# Sheet1.net
KiCad netlist of a schematic drawn in Altium Designer
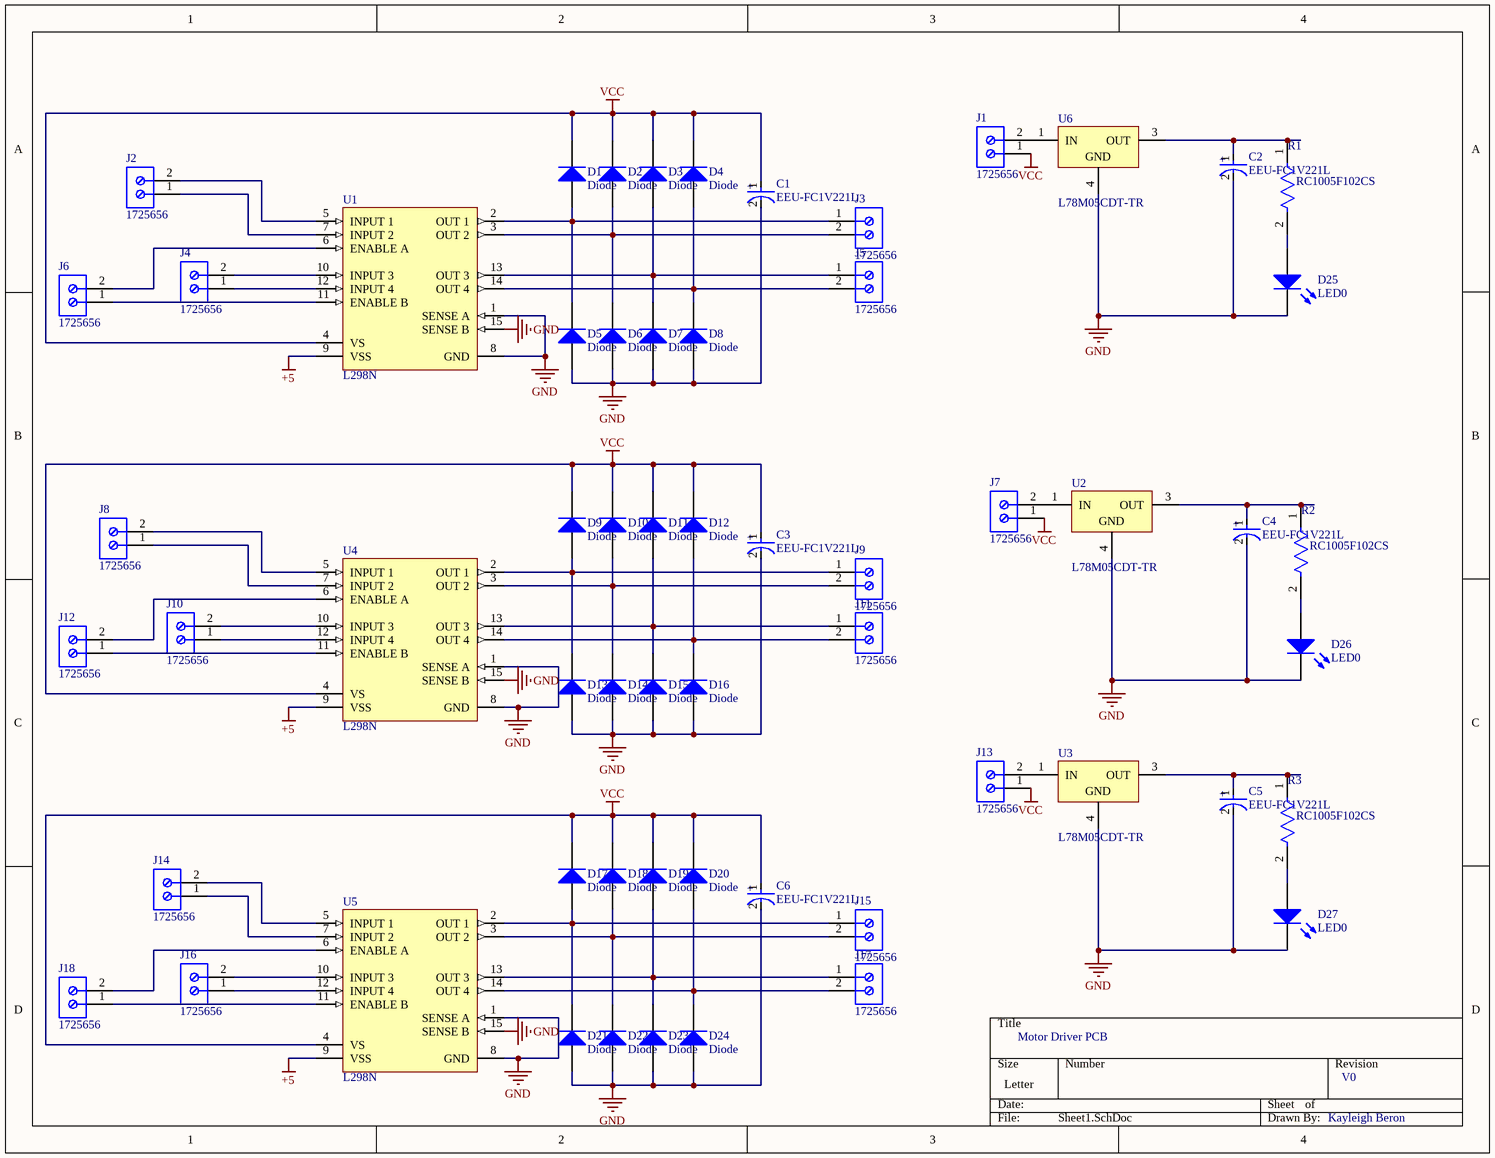
[diagram p0: Sheet1.SchDoc]

(export (version "E")
  (design (tool "Eeschema 10.0.6"))
  (components
    (comp (ref "C1")
      (value "EEU-FC1V221L")
      (footprint "FP-EEU-FC1V221L-MFG")
      (description "CAP ALUM 220UF 20% 35V RADIAL")
      (fields
        (field (name "OCTOPART") "https://octopart.com/eeu-fc1v221l-panasonic-39478519")
        (field (name "MANUFACTURER") "Panasonic Electronic Components")
      )
      (libsource (lib "Altium Content Vault") (part "385ce6c70a3ab0aa1e866f00bd8ed49"))
    )
    (comp (ref "C2")
      (value "EEU-FC1V221L")
      (footprint "FP-EEU-FC1V221L-MFG")
      (description "CAP ALUM 220UF 20% 35V RADIAL")
      (fields
        (field (name "OCTOPART") "https://octopart.com/eeu-fc1v221l-panasonic-39478519")
        (field (name "MANUFACTURER") "Panasonic Electronic Components")
      )
      (libsource (lib "Altium Content Vault") (part "385ce6c70a3ab0aa1e866f00bd8ed49"))
    )
    (comp (ref "C3")
      (value "EEU-FC1V221L")
      (footprint "FP-EEU-FC1V221L-MFG")
      (description "CAP ALUM 220UF 20% 35V RADIAL")
      (fields
        (field (name "OCTOPART") "https://octopart.com/eeu-fc1v221l-panasonic-39478519")
        (field (name "MANUFACTURER") "Panasonic Electronic Components")
      )
      (libsource (lib "Altium Content Vault") (part "385ce6c70a3ab0aa1e866f00bd8ed49"))
    )
    (comp (ref "C4")
      (value "EEU-FC1V221L")
      (footprint "FP-EEU-FC1V221L-MFG")
      (description "CAP ALUM 220UF 20% 35V RADIAL")
      (fields
        (field (name "OCTOPART") "https://octopart.com/eeu-fc1v221l-panasonic-39478519")
        (field (name "MANUFACTURER") "Panasonic Electronic Components")
      )
      (libsource (lib "Altium Content Vault") (part "385ce6c70a3ab0aa1e866f00bd8ed49"))
    )
    (comp (ref "C5")
      (value "EEU-FC1V221L")
      (footprint "FP-EEU-FC1V221L-MFG")
      (description "CAP ALUM 220UF 20% 35V RADIAL")
      (fields
        (field (name "OCTOPART") "https://octopart.com/eeu-fc1v221l-panasonic-39478519")
        (field (name "MANUFACTURER") "Panasonic Electronic Components")
      )
      (libsource (lib "Altium Content Vault") (part "385ce6c70a3ab0aa1e866f00bd8ed49"))
    )
    (comp (ref "C6")
      (value "EEU-FC1V221L")
      (footprint "FP-EEU-FC1V221L-MFG")
      (description "CAP ALUM 220UF 20% 35V RADIAL")
      (fields
        (field (name "OCTOPART") "https://octopart.com/eeu-fc1v221l-panasonic-39478519")
        (field (name "MANUFACTURER") "Panasonic Electronic Components")
      )
      (libsource (lib "Altium Content Vault") (part "385ce6c70a3ab0aa1e866f00bd8ed49"))
    )
    (comp (ref "D1")
      (value "Diode")
      (footprint "SMC")
      (description "Default Diode")
      (fields (field (name "PUBLISHER") "Altium Limited"))
      (libsource (lib "Miscellaneous Devices") (part "Diode"))
    )
    (comp (ref "D2")
      (value "Diode")
      (footprint "SMC")
      (description "Default Diode")
      (fields (field (name "PUBLISHER") "Altium Limited"))
      (libsource (lib "Miscellaneous Devices") (part "Diode"))
    )
    (comp (ref "D3")
      (value "Diode")
      (footprint "SMC")
      (description "Default Diode")
      (fields (field (name "PUBLISHER") "Altium Limited"))
      (libsource (lib "Miscellaneous Devices") (part "Diode"))
    )
    (comp (ref "D4")
      (value "Diode")
      (footprint "SMC")
      (description "Default Diode")
      (fields (field (name "PUBLISHER") "Altium Limited"))
      (libsource (lib "Miscellaneous Devices") (part "Diode"))
    )
    (comp (ref "D5")
      (value "Diode")
      (footprint "SMC")
      (description "Default Diode")
      (fields (field (name "PUBLISHER") "Altium Limited"))
      (libsource (lib "Miscellaneous Devices") (part "Diode"))
    )
    (comp (ref "D6")
      (value "Diode")
      (footprint "SMC")
      (description "Default Diode")
      (fields (field (name "PUBLISHER") "Altium Limited"))
      (libsource (lib "Miscellaneous Devices") (part "Diode"))
    )
    (comp (ref "D7")
      (value "Diode")
      (footprint "SMC")
      (description "Default Diode")
      (fields (field (name "PUBLISHER") "Altium Limited"))
      (libsource (lib "Miscellaneous Devices") (part "Diode"))
    )
    (comp (ref "D8")
      (value "Diode")
      (footprint "SMC")
      (description "Default Diode")
      (fields (field (name "PUBLISHER") "Altium Limited"))
      (libsource (lib "Miscellaneous Devices") (part "Diode"))
    )
    (comp (ref "D9")
      (value "Diode")
      (footprint "SMC")
      (description "Default Diode")
      (fields (field (name "PUBLISHER") "Altium Limited"))
      (libsource (lib "Miscellaneous Devices") (part "Diode"))
    )
    (comp (ref "D10")
      (value "Diode")
      (footprint "SMC")
      (description "Default Diode")
      (fields (field (name "PUBLISHER") "Altium Limited"))
      (libsource (lib "Miscellaneous Devices") (part "Diode"))
    )
    (comp (ref "D11")
      (value "Diode")
      (footprint "SMC")
      (description "Default Diode")
      (fields (field (name "PUBLISHER") "Altium Limited"))
      (libsource (lib "Miscellaneous Devices") (part "Diode"))
    )
    (comp (ref "D12")
      (value "Diode")
      (footprint "SMC")
      (description "Default Diode")
      (fields (field (name "PUBLISHER") "Altium Limited"))
      (libsource (lib "Miscellaneous Devices") (part "Diode"))
    )
    (comp (ref "D13")
      (value "Diode")
      (footprint "SMC")
      (description "Default Diode")
      (fields (field (name "PUBLISHER") "Altium Limited"))
      (libsource (lib "Miscellaneous Devices") (part "Diode"))
    )
    (comp (ref "D14")
      (value "Diode")
      (footprint "SMC")
      (description "Default Diode")
      (fields (field (name "PUBLISHER") "Altium Limited"))
      (libsource (lib "Miscellaneous Devices") (part "Diode"))
    )
    (comp (ref "D15")
      (value "Diode")
      (footprint "SMC")
      (description "Default Diode")
      (fields (field (name "PUBLISHER") "Altium Limited"))
      (libsource (lib "Miscellaneous Devices") (part "Diode"))
    )
    (comp (ref "D16")
      (value "Diode")
      (footprint "SMC")
      (description "Default Diode")
      (fields (field (name "PUBLISHER") "Altium Limited"))
      (libsource (lib "Miscellaneous Devices") (part "Diode"))
    )
    (comp (ref "D17")
      (value "Diode")
      (footprint "SMC")
      (description "Default Diode")
      (fields (field (name "PUBLISHER") "Altium Limited"))
      (libsource (lib "Miscellaneous Devices") (part "Diode"))
    )
    (comp (ref "D18")
      (value "Diode")
      (footprint "SMC")
      (description "Default Diode")
      (fields (field (name "PUBLISHER") "Altium Limited"))
      (libsource (lib "Miscellaneous Devices") (part "Diode"))
    )
    (comp (ref "D19")
      (value "Diode")
      (footprint "SMC")
      (description "Default Diode")
      (fields (field (name "PUBLISHER") "Altium Limited"))
      (libsource (lib "Miscellaneous Devices") (part "Diode"))
    )
    (comp (ref "D20")
      (value "Diode")
      (footprint "SMC")
      (description "Default Diode")
      (fields (field (name "PUBLISHER") "Altium Limited"))
      (libsource (lib "Miscellaneous Devices") (part "Diode"))
    )
    (comp (ref "D21")
      (value "Diode")
      (footprint "SMC")
      (description "Default Diode")
      (fields (field (name "PUBLISHER") "Altium Limited"))
      (libsource (lib "Miscellaneous Devices") (part "Diode"))
    )
    (comp (ref "D22")
      (value "Diode")
      (footprint "SMC")
      (description "Default Diode")
      (fields (field (name "PUBLISHER") "Altium Limited"))
      (libsource (lib "Miscellaneous Devices") (part "Diode"))
    )
    (comp (ref "D23")
      (value "Diode")
      (footprint "SMC")
      (description "Default Diode")
      (fields (field (name "PUBLISHER") "Altium Limited"))
      (libsource (lib "Miscellaneous Devices") (part "Diode"))
    )
    (comp (ref "D24")
      (value "Diode")
      (footprint "SMC")
      (description "Default Diode")
      (fields (field (name "PUBLISHER") "Altium Limited"))
      (libsource (lib "Miscellaneous Devices") (part "Diode"))
    )
    (comp (ref "D25")
      (value "LED0")
      (footprint "LED-0")
      (description "Typical INFRARED GaAs LED")
      (fields (field (name "PUBLISHER") "Altium Limited"))
      (libsource (lib "Miscellaneous Devices") (part "LED0"))
    )
    (comp (ref "D26")
      (value "LED0")
      (footprint "LED-0")
      (description "Typical INFRARED GaAs LED")
      (fields (field (name "PUBLISHER") "Altium Limited"))
      (libsource (lib "Miscellaneous Devices") (part "LED0"))
    )
    (comp (ref "D27")
      (value "LED0")
      (footprint "LED-0")
      (description "Typical INFRARED GaAs LED")
      (fields (field (name "PUBLISHER") "Altium Limited"))
      (libsource (lib "Miscellaneous Devices") (part "LED0"))
    )
    (comp (ref "J1")
      (value "1725656")
      (footprint "PHOE-1725656-2")
      (description "Male Header, Pitch 2.54 mm, 1 x 2 Position, Height 9 mm, Tail Length 3.5 mm")
      (fields (field (name "MANUFACTURER") "Phoenix Contact"))
      (libsource (lib "Altium Content Vault") (part "CN-1P-F-TB2"))
    )
    (comp (ref "J2")
      (value "1725656")
      (footprint "PHOE-1725656-2")
      (description "Male Header, Pitch 2.54 mm, 1 x 2 Position, Height 9 mm, Tail Length 3.5 mm")
      (fields (field (name "MANUFACTURER") "Phoenix Contact"))
      (libsource (lib "Altium Content Vault") (part "CN-1P-F-TB2"))
    )
    (comp (ref "J3")
      (value "1725656")
      (footprint "PHOE-1725656-2")
      (description "Male Header, Pitch 2.54 mm, 1 x 2 Position, Height 9 mm, Tail Length 3.5 mm")
      (fields (field (name "MANUFACTURER") "Phoenix Contact"))
      (libsource (lib "Altium Content Vault") (part "CN-1P-F-TB2"))
    )
    (comp (ref "J4")
      (value "1725656")
      (footprint "PHOE-1725656-2")
      (description "Male Header, Pitch 2.54 mm, 1 x 2 Position, Height 9 mm, Tail Length 3.5 mm")
      (fields (field (name "MANUFACTURER") "Phoenix Contact"))
      (libsource (lib "Altium Content Vault") (part "CN-1P-F-TB2"))
    )
    (comp (ref "J5")
      (value "1725656")
      (footprint "PHOE-1725656-2")
      (description "Male Header, Pitch 2.54 mm, 1 x 2 Position, Height 9 mm, Tail Length 3.5 mm")
      (fields (field (name "MANUFACTURER") "Phoenix Contact"))
      (libsource (lib "Altium Content Vault") (part "CN-1P-F-TB2"))
    )
    (comp (ref "J6")
      (value "1725656")
      (footprint "PHOE-1725656-2")
      (description "Male Header, Pitch 2.54 mm, 1 x 2 Position, Height 9 mm, Tail Length 3.5 mm")
      (fields (field (name "MANUFACTURER") "Phoenix Contact"))
      (libsource (lib "Altium Content Vault") (part "CN-1P-F-TB2"))
    )
    (comp (ref "J7")
      (value "1725656")
      (footprint "PHOE-1725656-2")
      (description "Male Header, Pitch 2.54 mm, 1 x 2 Position, Height 9 mm, Tail Length 3.5 mm")
      (fields (field (name "MANUFACTURER") "Phoenix Contact"))
      (libsource (lib "Altium Content Vault") (part "CN-1P-F-TB2"))
    )
    (comp (ref "J8")
      (value "1725656")
      (footprint "PHOE-1725656-2")
      (description "Male Header, Pitch 2.54 mm, 1 x 2 Position, Height 9 mm, Tail Length 3.5 mm")
      (fields (field (name "MANUFACTURER") "Phoenix Contact"))
      (libsource (lib "Altium Content Vault") (part "CN-1P-F-TB2"))
    )
    (comp (ref "J9")
      (value "1725656")
      (footprint "PHOE-1725656-2")
      (description "Male Header, Pitch 2.54 mm, 1 x 2 Position, Height 9 mm, Tail Length 3.5 mm")
      (fields (field (name "MANUFACTURER") "Phoenix Contact"))
      (libsource (lib "Altium Content Vault") (part "CN-1P-F-TB2"))
    )
    (comp (ref "J10")
      (value "1725656")
      (footprint "PHOE-1725656-2")
      (description "Male Header, Pitch 2.54 mm, 1 x 2 Position, Height 9 mm, Tail Length 3.5 mm")
      (fields (field (name "MANUFACTURER") "Phoenix Contact"))
      (libsource (lib "Altium Content Vault") (part "CN-1P-F-TB2"))
    )
    (comp (ref "J11")
      (value "1725656")
      (footprint "PHOE-1725656-2")
      (description "Male Header, Pitch 2.54 mm, 1 x 2 Position, Height 9 mm, Tail Length 3.5 mm")
      (fields (field (name "MANUFACTURER") "Phoenix Contact"))
      (libsource (lib "Altium Content Vault") (part "CN-1P-F-TB2"))
    )
    (comp (ref "J12")
      (value "1725656")
      (footprint "PHOE-1725656-2")
      (description "Male Header, Pitch 2.54 mm, 1 x 2 Position, Height 9 mm, Tail Length 3.5 mm")
      (fields (field (name "MANUFACTURER") "Phoenix Contact"))
      (libsource (lib "Altium Content Vault") (part "CN-1P-F-TB2"))
    )
    (comp (ref "J13")
      (value "1725656")
      (footprint "PHOE-1725656-2")
      (description "Male Header, Pitch 2.54 mm, 1 x 2 Position, Height 9 mm, Tail Length 3.5 mm")
      (fields (field (name "MANUFACTURER") "Phoenix Contact"))
      (libsource (lib "Altium Content Vault") (part "CN-1P-F-TB2"))
    )
    (comp (ref "J14")
      (value "1725656")
      (footprint "PHOE-1725656-2")
      (description "Male Header, Pitch 2.54 mm, 1 x 2 Position, Height 9 mm, Tail Length 3.5 mm")
      (fields (field (name "MANUFACTURER") "Phoenix Contact"))
      (libsource (lib "Altium Content Vault") (part "CN-1P-F-TB2"))
    )
    (comp (ref "J15")
      (value "1725656")
      (footprint "PHOE-1725656-2")
      (description "Male Header, Pitch 2.54 mm, 1 x 2 Position, Height 9 mm, Tail Length 3.5 mm")
      (fields (field (name "MANUFACTURER") "Phoenix Contact"))
      (libsource (lib "Altium Content Vault") (part "CN-1P-F-TB2"))
    )
    (comp (ref "J16")
      (value "1725656")
      (footprint "PHOE-1725656-2")
      (description "Male Header, Pitch 2.54 mm, 1 x 2 Position, Height 9 mm, Tail Length 3.5 mm")
      (fields (field (name "MANUFACTURER") "Phoenix Contact"))
      (libsource (lib "Altium Content Vault") (part "CN-1P-F-TB2"))
    )
    (comp (ref "J17")
      (value "1725656")
      (footprint "PHOE-1725656-2")
      (description "Male Header, Pitch 2.54 mm, 1 x 2 Position, Height 9 mm, Tail Length 3.5 mm")
      (fields (field (name "MANUFACTURER") "Phoenix Contact"))
      (libsource (lib "Altium Content Vault") (part "CN-1P-F-TB2"))
    )
    (comp (ref "J18")
      (value "1725656")
      (footprint "PHOE-1725656-2")
      (description "Male Header, Pitch 2.54 mm, 1 x 2 Position, Height 9 mm, Tail Length 3.5 mm")
      (fields (field (name "MANUFACTURER") "Phoenix Contact"))
      (libsource (lib "Altium Content Vault") (part "CN-1P-F-TB2"))
    )
    (comp (ref "R1")
      (value "RC1005F102CS")
      (footprint "FP-RC1005-IPC_A")
      (description "Res Thick Film 0402 1kΩ 1% 0.063W ±100ppm/°C Molded SMD T/R")
      (fields (field (name "TOLERANCE") "1%"))
      (libsource (lib "Altium Content Vault") (part "1029c3af85768c4190bb7ad29bc67b5"))
    )
    (comp (ref "R2")
      (value "RC1005F102CS")
      (footprint "FP-RC1005-IPC_A")
      (description "Res Thick Film 0402 1kΩ 1% 0.063W ±100ppm/°C Molded SMD T/R")
      (fields (field (name "TOLERANCE") "1%"))
      (libsource (lib "Altium Content Vault") (part "1029c3af85768c4190bb7ad29bc67b5"))
    )
    (comp (ref "R3")
      (value "RC1005F102CS")
      (footprint "FP-RC1005-IPC_A")
      (description "Res Thick Film 0402 1kΩ 1% 0.063W ±100ppm/°C Molded SMD T/R")
      (fields (field (name "TOLERANCE") "1%"))
      (libsource (lib "Altium Content Vault") (part "1029c3af85768c4190bb7ad29bc67b5"))
    )
    (comp (ref "U1")
      (value "L298N")
      (footprint "STM-FM-15")
      (description "Dual Full-Bridge Driver, 4.8 to 46 V, -40 to 150 degC, 15-Pin FM (MW 15L), RoHS, Tube")
      (fields (field (name "MANUFACTURER") "STMicroelectronics") (field (name "PARTNUMBER") "L298"))
      (libsource (lib "Altium Content Vault") (part "STM-L298-15"))
    )
    (comp (ref "U2")
      (value "L78M05CDT-TR")
      (footprint "TO-252_L")
      (description "Positive Voltage Regulator, 5V, 3-Pin DPAK, Tape and Reel")
      (libsource (lib "Altium Content Vault") (part "PM-REG-L4940-SOT3"))
    )
    (comp (ref "U3")
      (value "L78M05CDT-TR")
      (footprint "TO-252_L")
      (description "Positive Voltage Regulator, 5V, 3-Pin DPAK, Tape and Reel")
      (libsource (lib "Altium Content Vault") (part "PM-REG-L4940-SOT3"))
    )
    (comp (ref "U4")
      (value "L298N")
      (footprint "STM-FM-15")
      (description "Dual Full-Bridge Driver, 4.8 to 46 V, -40 to 150 degC, 15-Pin FM (MW 15L), RoHS, Tube")
      (fields (field (name "MANUFACTURER") "STMicroelectronics") (field (name "PARTNUMBER") "L298"))
      (libsource (lib "Altium Content Vault") (part "STM-L298-15"))
    )
    (comp (ref "U5")
      (value "L298N")
      (footprint "STM-FM-15")
      (description "Dual Full-Bridge Driver, 4.8 to 46 V, -40 to 150 degC, 15-Pin FM (MW 15L), RoHS, Tube")
      (fields (field (name "MANUFACTURER") "STMicroelectronics") (field (name "PARTNUMBER") "L298"))
      (libsource (lib "Altium Content Vault") (part "STM-L298-15"))
    )
    (comp (ref "U6")
      (value "L78M05CDT-TR")
      (footprint "TO-252_L")
      (description "Positive Voltage Regulator, 5V, 3-Pin DPAK, Tape and Reel")
      (libsource (lib "Altium Content Vault") (part "PM-REG-L4940-SOT3"))
    )
  )
  (nets
    (net (code "1") (name "+5") (class "Default")
      (node (ref "U1") (pin "9") (pinfunction "VSS_9") (pintype "power_in"))
      (node (ref "U4") (pin "9") (pinfunction "VSS_9") (pintype "power_in"))
      (node (ref "U5") (pin "9") (pinfunction "VSS_9") (pintype "power_in"))
    )
    (net (code "2") (name "GND") (class "Default")
      (node (ref "C1") (pin "2") (pinfunction "A_2") (pintype "passive"))
      (node (ref "C2") (pin "2") (pinfunction "A_2") (pintype "passive"))
      (node (ref "C3") (pin "2") (pinfunction "A_2") (pintype "passive"))
      (node (ref "C4") (pin "2") (pinfunction "A_2") (pintype "passive"))
      (node (ref "C5") (pin "2") (pinfunction "A_2") (pintype "passive"))
      (node (ref "C6") (pin "2") (pinfunction "A_2") (pintype "passive"))
      (node (ref "D13") (pin "1") (pinfunction "A_1") (pintype "passive"))
      (node (ref "D14") (pin "1") (pinfunction "A_1") (pintype "passive"))
      (node (ref "D15") (pin "1") (pinfunction "A_1") (pintype "passive"))
      (node (ref "D16") (pin "1") (pinfunction "A_1") (pintype "passive"))
      (node (ref "D21") (pin "1") (pinfunction "A_1") (pintype "passive"))
      (node (ref "D22") (pin "1") (pinfunction "A_1") (pintype "passive"))
      (node (ref "D23") (pin "1") (pinfunction "A_1") (pintype "passive"))
      (node (ref "D24") (pin "1") (pinfunction "A_1") (pintype "passive"))
      (node (ref "D25") (pin "2") (pinfunction "K_2") (pintype "passive"))
      (node (ref "D26") (pin "2") (pinfunction "K_2") (pintype "passive"))
      (node (ref "D27") (pin "2") (pinfunction "K_2") (pintype "passive"))
      (node (ref "D5") (pin "1") (pinfunction "A_1") (pintype "passive"))
      (node (ref "D6") (pin "1") (pinfunction "A_1") (pintype "passive"))
      (node (ref "D7") (pin "1") (pinfunction "A_1") (pintype "passive"))
      (node (ref "D8") (pin "1") (pinfunction "A_1") (pintype "passive"))
      (node (ref "U1") (pin "1") (pinfunction "SENSE_A_1") (pintype "input"))
      (node (ref "U1") (pin "15") (pinfunction "SENSE_B_15") (pintype "input"))
      (node (ref "U1") (pin "8") (pinfunction "GND_8") (pintype "power_in"))
      (node (ref "U2") (pin "4") (pinfunction "GND_4") (pintype "power_in"))
      (node (ref "U3") (pin "4") (pinfunction "GND_4") (pintype "power_in"))
      (node (ref "U4") (pin "1") (pinfunction "SENSE_A_1") (pintype "input"))
      (node (ref "U4") (pin "15") (pinfunction "SENSE_B_15") (pintype "input"))
      (node (ref "U4") (pin "8") (pinfunction "GND_8") (pintype "power_in"))
      (node (ref "U5") (pin "1") (pinfunction "SENSE_A_1") (pintype "input"))
      (node (ref "U5") (pin "15") (pinfunction "SENSE_B_15") (pintype "input"))
      (node (ref "U5") (pin "8") (pinfunction "GND_8") (pintype "power_in"))
      (node (ref "U6") (pin "4") (pinfunction "GND_4") (pintype "power_in"))
    )
    (net (code "3") (name "Net-(C2-C)") (class "Default")
      (node (ref "C2") (pin "1") (pinfunction "C_1") (pintype "passive"))
      (node (ref "R1") (pin "1") (pinfunction "1_1") (pintype "passive"))
      (node (ref "U6") (pin "3") (pinfunction "OUT_3") (pintype "power_in"))
    )
    (net (code "4") (name "Net-(C4-C)") (class "Default")
      (node (ref "C4") (pin "1") (pinfunction "C_1") (pintype "passive"))
      (node (ref "R2") (pin "1") (pinfunction "1_1") (pintype "passive"))
      (node (ref "U2") (pin "3") (pinfunction "OUT_3") (pintype "power_in"))
    )
    (net (code "5") (name "Net-(C5-C)") (class "Default")
      (node (ref "C5") (pin "1") (pinfunction "C_1") (pintype "passive"))
      (node (ref "R3") (pin "1") (pinfunction "1_1") (pintype "passive"))
      (node (ref "U3") (pin "3") (pinfunction "OUT_3") (pintype "power_in"))
    )
    (net (code "6") (name "Net-(D1-A)") (class "Default")
      (node (ref "D1") (pin "1") (pinfunction "A_1") (pintype "passive"))
      (node (ref "D5") (pin "2") (pinfunction "K_2") (pintype "passive"))
      (node (ref "J3") (pin "1") (pinfunction "1_1") (pintype "passive"))
      (node (ref "U1") (pin "2") (pinfunction "OUT_1_2") (pintype "output"))
    )
    (net (code "7") (name "Net-(D2-A)") (class "Default")
      (node (ref "D2") (pin "1") (pinfunction "A_1") (pintype "passive"))
      (node (ref "D6") (pin "2") (pinfunction "K_2") (pintype "passive"))
      (node (ref "J3") (pin "2") (pinfunction "2_2") (pintype "passive"))
      (node (ref "U1") (pin "3") (pinfunction "OUT_2_3") (pintype "output"))
    )
    (net (code "8") (name "Net-(D3-A)") (class "Default")
      (node (ref "D3") (pin "1") (pinfunction "A_1") (pintype "passive"))
      (node (ref "D7") (pin "2") (pinfunction "K_2") (pintype "passive"))
      (node (ref "J5") (pin "1") (pinfunction "1_1") (pintype "passive"))
      (node (ref "U1") (pin "13") (pinfunction "OUT_3_13") (pintype "output"))
    )
    (net (code "9") (name "Net-(D4-A)") (class "Default")
      (node (ref "D4") (pin "1") (pinfunction "A_1") (pintype "passive"))
      (node (ref "D8") (pin "2") (pinfunction "K_2") (pintype "passive"))
      (node (ref "J5") (pin "2") (pinfunction "2_2") (pintype "passive"))
      (node (ref "U1") (pin "14") (pinfunction "OUT_4_14") (pintype "output"))
    )
    (net (code "10") (name "Net-(D10-A)") (class "Default")
      (node (ref "D10") (pin "1") (pinfunction "A_1") (pintype "passive"))
      (node (ref "D14") (pin "2") (pinfunction "K_2") (pintype "passive"))
      (node (ref "J9") (pin "2") (pinfunction "2_2") (pintype "passive"))
      (node (ref "U4") (pin "3") (pinfunction "OUT_2_3") (pintype "output"))
    )
    (net (code "11") (name "Net-(D11-A)") (class "Default")
      (node (ref "D11") (pin "1") (pinfunction "A_1") (pintype "passive"))
      (node (ref "D15") (pin "2") (pinfunction "K_2") (pintype "passive"))
      (node (ref "J11") (pin "1") (pinfunction "1_1") (pintype "passive"))
      (node (ref "U4") (pin "13") (pinfunction "OUT_3_13") (pintype "output"))
    )
    (net (code "12") (name "Net-(D12-A)") (class "Default")
      (node (ref "D12") (pin "1") (pinfunction "A_1") (pintype "passive"))
      (node (ref "D16") (pin "2") (pinfunction "K_2") (pintype "passive"))
      (node (ref "J11") (pin "2") (pinfunction "2_2") (pintype "passive"))
      (node (ref "U4") (pin "14") (pinfunction "OUT_4_14") (pintype "output"))
    )
    (net (code "13") (name "Net-(D13-K)") (class "Default")
      (node (ref "D13") (pin "2") (pinfunction "K_2") (pintype "passive"))
      (node (ref "D9") (pin "1") (pinfunction "A_1") (pintype "passive"))
      (node (ref "J9") (pin "1") (pinfunction "1_1") (pintype "passive"))
      (node (ref "U4") (pin "2") (pinfunction "OUT_1_2") (pintype "output"))
    )
    (net (code "14") (name "Net-(D17-A)") (class "Default")
      (node (ref "D17") (pin "1") (pinfunction "A_1") (pintype "passive"))
      (node (ref "D21") (pin "2") (pinfunction "K_2") (pintype "passive"))
      (node (ref "J15") (pin "1") (pinfunction "1_1") (pintype "passive"))
      (node (ref "U5") (pin "2") (pinfunction "OUT_1_2") (pintype "output"))
    )
    (net (code "15") (name "Net-(D18-A)") (class "Default")
      (node (ref "D18") (pin "1") (pinfunction "A_1") (pintype "passive"))
      (node (ref "D22") (pin "2") (pinfunction "K_2") (pintype "passive"))
      (node (ref "J15") (pin "2") (pinfunction "2_2") (pintype "passive"))
      (node (ref "U5") (pin "3") (pinfunction "OUT_2_3") (pintype "output"))
    )
    (net (code "16") (name "Net-(D19-A)") (class "Default")
      (node (ref "D19") (pin "1") (pinfunction "A_1") (pintype "passive"))
      (node (ref "D23") (pin "2") (pinfunction "K_2") (pintype "passive"))
      (node (ref "J17") (pin "1") (pinfunction "1_1") (pintype "passive"))
      (node (ref "U5") (pin "13") (pinfunction "OUT_3_13") (pintype "output"))
    )
    (net (code "17") (name "Net-(D20-A)") (class "Default")
      (node (ref "D20") (pin "1") (pinfunction "A_1") (pintype "passive"))
      (node (ref "D24") (pin "2") (pinfunction "K_2") (pintype "passive"))
      (node (ref "J17") (pin "2") (pinfunction "2_2") (pintype "passive"))
      (node (ref "U5") (pin "14") (pinfunction "OUT_4_14") (pintype "output"))
    )
    (net (code "18") (name "Net-(D25-A)") (class "Default")
      (node (ref "D25") (pin "1") (pinfunction "A_1") (pintype "passive"))
      (node (ref "R1") (pin "2") (pinfunction "2_2") (pintype "passive"))
    )
    (net (code "19") (name "Net-(D26-A)") (class "Default")
      (node (ref "D26") (pin "1") (pinfunction "A_1") (pintype "passive"))
      (node (ref "R2") (pin "2") (pinfunction "2_2") (pintype "passive"))
    )
    (net (code "20") (name "Net-(D27-A)") (class "Default")
      (node (ref "D27") (pin "1") (pinfunction "A_1") (pintype "passive"))
      (node (ref "R3") (pin "2") (pinfunction "2_2") (pintype "passive"))
    )
    (net (code "21") (name "Net-(U1-ENABLE_A)") (class "Default")
      (node (ref "J6") (pin "2") (pinfunction "2_2") (pintype "passive"))
      (node (ref "U1") (pin "6") (pinfunction "ENABLE_A_6") (pintype "input"))
    )
    (net (code "22") (name "Net-(U1-ENABLE_B)") (class "Default")
      (node (ref "J6") (pin "1") (pinfunction "1_1") (pintype "passive"))
      (node (ref "U1") (pin "11") (pinfunction "ENABLE_B_11") (pintype "input"))
    )
    (net (code "23") (name "Net-(U1-INPUT_1)") (class "Default")
      (node (ref "J2") (pin "2") (pinfunction "2_2") (pintype "passive"))
      (node (ref "U1") (pin "5") (pinfunction "INPUT_1_5") (pintype "input"))
    )
    (net (code "24") (name "Net-(U1-INPUT_2)") (class "Default")
      (node (ref "J2") (pin "1") (pinfunction "1_1") (pintype "passive"))
      (node (ref "U1") (pin "7") (pinfunction "INPUT_2_7") (pintype "input"))
    )
    (net (code "25") (name "Net-(U1-INPUT_3)") (class "Default")
      (node (ref "J4") (pin "2") (pinfunction "2_2") (pintype "passive"))
      (node (ref "U1") (pin "10") (pinfunction "INPUT_3_10") (pintype "input"))
    )
    (net (code "26") (name "Net-(U1-INPUT_4)") (class "Default")
      (node (ref "J4") (pin "1") (pinfunction "1_1") (pintype "passive"))
      (node (ref "U1") (pin "12") (pinfunction "INPUT_4_12") (pintype "input"))
    )
    (net (code "27") (name "Net-(U2-IN)") (class "Default")
      (node (ref "J7") (pin "2") (pinfunction "2_2") (pintype "passive"))
      (node (ref "U2") (pin "1") (pinfunction "IN_1") (pintype "power_in"))
    )
    (net (code "28") (name "Net-(U3-IN)") (class "Default")
      (node (ref "J13") (pin "2") (pinfunction "2_2") (pintype "passive"))
      (node (ref "U3") (pin "1") (pinfunction "IN_1") (pintype "power_in"))
    )
    (net (code "29") (name "Net-(U4-ENABLE_A)") (class "Default")
      (node (ref "J12") (pin "2") (pinfunction "2_2") (pintype "passive"))
      (node (ref "U4") (pin "6") (pinfunction "ENABLE_A_6") (pintype "input"))
    )
    (net (code "30") (name "Net-(U4-ENABLE_B)") (class "Default")
      (node (ref "J12") (pin "1") (pinfunction "1_1") (pintype "passive"))
      (node (ref "U4") (pin "11") (pinfunction "ENABLE_B_11") (pintype "input"))
    )
    (net (code "31") (name "Net-(U4-INPUT_1)") (class "Default")
      (node (ref "J8") (pin "2") (pinfunction "2_2") (pintype "passive"))
      (node (ref "U4") (pin "5") (pinfunction "INPUT_1_5") (pintype "input"))
    )
    (net (code "32") (name "Net-(U4-INPUT_2)") (class "Default")
      (node (ref "J8") (pin "1") (pinfunction "1_1") (pintype "passive"))
      (node (ref "U4") (pin "7") (pinfunction "INPUT_2_7") (pintype "input"))
    )
    (net (code "33") (name "Net-(U4-INPUT_3)") (class "Default")
      (node (ref "J10") (pin "2") (pinfunction "2_2") (pintype "passive"))
      (node (ref "U4") (pin "10") (pinfunction "INPUT_3_10") (pintype "input"))
    )
    (net (code "34") (name "Net-(U4-INPUT_4)") (class "Default")
      (node (ref "J10") (pin "1") (pinfunction "1_1") (pintype "passive"))
      (node (ref "U4") (pin "12") (pinfunction "INPUT_4_12") (pintype "input"))
    )
    (net (code "35") (name "Net-(U5-ENABLE_A)") (class "Default")
      (node (ref "J18") (pin "2") (pinfunction "2_2") (pintype "passive"))
      (node (ref "U5") (pin "6") (pinfunction "ENABLE_A_6") (pintype "input"))
    )
    (net (code "36") (name "Net-(U5-ENABLE_B)") (class "Default")
      (node (ref "J18") (pin "1") (pinfunction "1_1") (pintype "passive"))
      (node (ref "U5") (pin "11") (pinfunction "ENABLE_B_11") (pintype "input"))
    )
    (net (code "37") (name "Net-(U5-INPUT_1)") (class "Default")
      (node (ref "J14") (pin "2") (pinfunction "2_2") (pintype "passive"))
      (node (ref "U5") (pin "5") (pinfunction "INPUT_1_5") (pintype "input"))
    )
    (net (code "38") (name "Net-(U5-INPUT_2)") (class "Default")
      (node (ref "J14") (pin "1") (pinfunction "1_1") (pintype "passive"))
      (node (ref "U5") (pin "7") (pinfunction "INPUT_2_7") (pintype "input"))
    )
    (net (code "39") (name "Net-(U5-INPUT_3)") (class "Default")
      (node (ref "J16") (pin "2") (pinfunction "2_2") (pintype "passive"))
      (node (ref "U5") (pin "10") (pinfunction "INPUT_3_10") (pintype "input"))
    )
    (net (code "40") (name "Net-(U5-INPUT_4)") (class "Default")
      (node (ref "J16") (pin "1") (pinfunction "1_1") (pintype "passive"))
      (node (ref "U5") (pin "12") (pinfunction "INPUT_4_12") (pintype "input"))
    )
    (net (code "41") (name "Net-(U6-IN)") (class "Default")
      (node (ref "J1") (pin "2") (pinfunction "2_2") (pintype "passive"))
      (node (ref "U6") (pin "1") (pinfunction "IN_1") (pintype "power_in"))
    )
    (net (code "42") (name "VCC") (class "Default")
      (node (ref "C1") (pin "1") (pinfunction "C_1") (pintype "passive"))
      (node (ref "C3") (pin "1") (pinfunction "C_1") (pintype "passive"))
      (node (ref "C6") (pin "1") (pinfunction "C_1") (pintype "passive"))
      (node (ref "D1") (pin "2") (pinfunction "K_2") (pintype "passive"))
      (node (ref "D10") (pin "2") (pinfunction "K_2") (pintype "passive"))
      (node (ref "D11") (pin "2") (pinfunction "K_2") (pintype "passive"))
      (node (ref "D12") (pin "2") (pinfunction "K_2") (pintype "passive"))
      (node (ref "D17") (pin "2") (pinfunction "K_2") (pintype "passive"))
      (node (ref "D18") (pin "2") (pinfunction "K_2") (pintype "passive"))
      (node (ref "D19") (pin "2") (pinfunction "K_2") (pintype "passive"))
      (node (ref "D2") (pin "2") (pinfunction "K_2") (pintype "passive"))
      (node (ref "D20") (pin "2") (pinfunction "K_2") (pintype "passive"))
      (node (ref "D3") (pin "2") (pinfunction "K_2") (pintype "passive"))
      (node (ref "D4") (pin "2") (pinfunction "K_2") (pintype "passive"))
      (node (ref "D9") (pin "2") (pinfunction "K_2") (pintype "passive"))
      (node (ref "J1") (pin "1") (pinfunction "1_1") (pintype "passive"))
      (node (ref "J13") (pin "1") (pinfunction "1_1") (pintype "passive"))
      (node (ref "J7") (pin "1") (pinfunction "1_1") (pintype "passive"))
      (node (ref "U1") (pin "4") (pinfunction "VS_4") (pintype "power_in"))
      (node (ref "U4") (pin "4") (pinfunction "VS_4") (pintype "power_in"))
      (node (ref "U5") (pin "4") (pinfunction "VS_4") (pintype "power_in"))
    )
  )
)
